# VU_LED.net
KiCad netlist of a schematic drawn in Altium Designer
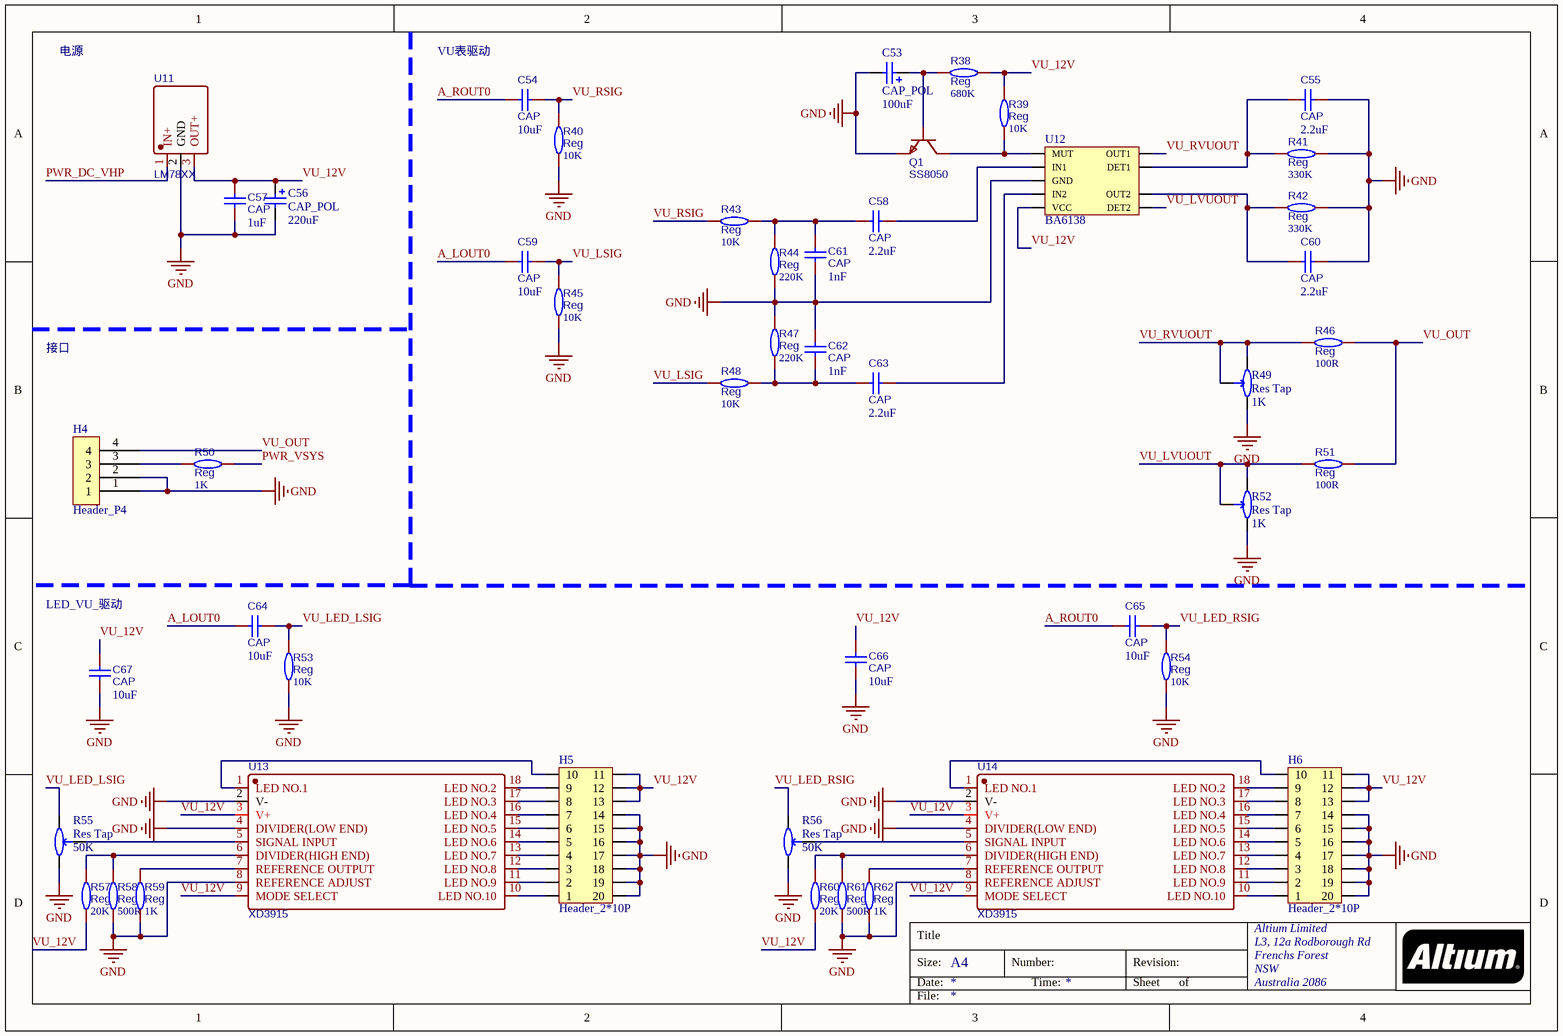
[diagram p0: VU_LED.SchDoc]

(export (version "E")
  (design (tool "Eeschema 10.0.6"))
  (components
    (comp (ref "C53")
      (value "CAP_POL")
      (footprint "CAP_SMD_6.3mm")
      (description "极性电容")
      (fields (field (name "ALTIUM_VALUE") "100uF"))
      (libsource (lib "Levent_lib") (part "CAP_POL"))
    )
    (comp (ref "C54")
      (value "CAP")
      (footprint "C0603")
      (description "Cap")
      (fields
        (field (name "BOM_SUPPLIER PART") "C302008")
        (field (name "BOM_MANUFACTURER PART") "0603B103K101CT")
        (field (name "ALTIUM_VALUE") "10uF")
        (field (name "CONTRIBUTOR") "LCSC")
      )
      (libsource (lib "Levent_lib") (part "CAP"))
    )
    (comp (ref "C55")
      (value "CAP")
      (footprint "C0603")
      (description "Cap")
      (fields
        (field (name "BOM_SUPPLIER PART") "C302008")
        (field (name "BOM_MANUFACTURER PART") "0603B103K101CT")
        (field (name "ALTIUM_VALUE") "2.2uF")
        (field (name "CONTRIBUTOR") "LCSC")
      )
      (libsource (lib "Levent_lib") (part "CAP"))
    )
    (comp (ref "C56")
      (value "CAP_POL")
      (footprint "CAP_SMD_6.3mm")
      (description "极性电容")
      (fields (field (name "ALTIUM_VALUE") "220uF"))
      (libsource (lib "Levent_lib") (part "CAP_POL"))
    )
    (comp (ref "C57")
      (value "CAP")
      (footprint "C0603")
      (description "Cap")
      (fields
        (field (name "BOM_SUPPLIER PART") "C302008")
        (field (name "BOM_MANUFACTURER PART") "0603B103K101CT")
        (field (name "ALTIUM_VALUE") "1uF")
        (field (name "CONTRIBUTOR") "LCSC")
      )
      (libsource (lib "Levent_lib") (part "CAP"))
    )
    (comp (ref "C58")
      (value "CAP")
      (footprint "C0603")
      (description "Cap")
      (fields
        (field (name "BOM_SUPPLIER PART") "C302008")
        (field (name "BOM_MANUFACTURER PART") "0603B103K101CT")
        (field (name "ALTIUM_VALUE") "2.2uF")
        (field (name "CONTRIBUTOR") "LCSC")
      )
      (libsource (lib "Levent_lib") (part "CAP"))
    )
    (comp (ref "C59")
      (value "CAP")
      (footprint "C0603")
      (description "Cap")
      (fields
        (field (name "BOM_SUPPLIER PART") "C302008")
        (field (name "BOM_MANUFACTURER PART") "0603B103K101CT")
        (field (name "ALTIUM_VALUE") "10uF")
        (field (name "CONTRIBUTOR") "LCSC")
      )
      (libsource (lib "Levent_lib") (part "CAP"))
    )
    (comp (ref "C60")
      (value "CAP")
      (footprint "C0603")
      (description "Cap")
      (fields
        (field (name "BOM_SUPPLIER PART") "C302008")
        (field (name "BOM_MANUFACTURER PART") "0603B103K101CT")
        (field (name "ALTIUM_VALUE") "2.2uF")
        (field (name "CONTRIBUTOR") "LCSC")
      )
      (libsource (lib "Levent_lib") (part "CAP"))
    )
    (comp (ref "C61")
      (value "CAP")
      (footprint "C0603")
      (description "Cap")
      (fields
        (field (name "BOM_SUPPLIER PART") "C302008")
        (field (name "BOM_MANUFACTURER PART") "0603B103K101CT")
        (field (name "ALTIUM_VALUE") "1nF")
        (field (name "CONTRIBUTOR") "LCSC")
      )
      (libsource (lib "Levent_lib") (part "CAP"))
    )
    (comp (ref "C62")
      (value "CAP")
      (footprint "C0603")
      (description "Cap")
      (fields
        (field (name "BOM_SUPPLIER PART") "C302008")
        (field (name "BOM_MANUFACTURER PART") "0603B103K101CT")
        (field (name "ALTIUM_VALUE") "1nF")
        (field (name "CONTRIBUTOR") "LCSC")
      )
      (libsource (lib "Levent_lib") (part "CAP"))
    )
    (comp (ref "C63")
      (value "CAP")
      (footprint "C0603")
      (description "Cap")
      (fields
        (field (name "BOM_SUPPLIER PART") "C302008")
        (field (name "BOM_MANUFACTURER PART") "0603B103K101CT")
        (field (name "ALTIUM_VALUE") "2.2uF")
        (field (name "CONTRIBUTOR") "LCSC")
      )
      (libsource (lib "Levent_lib") (part "CAP"))
    )
    (comp (ref "C64")
      (value "CAP")
      (footprint "C0603")
      (description "Cap")
      (fields
        (field (name "BOM_SUPPLIER PART") "C302008")
        (field (name "BOM_MANUFACTURER PART") "0603B103K101CT")
        (field (name "ALTIUM_VALUE") "10uF")
        (field (name "CONTRIBUTOR") "LCSC")
      )
      (libsource (lib "Levent_lib") (part "CAP"))
    )
    (comp (ref "C65")
      (value "CAP")
      (footprint "C0603")
      (description "Cap")
      (fields
        (field (name "BOM_SUPPLIER PART") "C302008")
        (field (name "BOM_MANUFACTURER PART") "0603B103K101CT")
        (field (name "ALTIUM_VALUE") "10uF")
        (field (name "CONTRIBUTOR") "LCSC")
      )
      (libsource (lib "Levent_lib") (part "CAP"))
    )
    (comp (ref "C66")
      (value "CAP")
      (footprint "C0603")
      (description "Cap")
      (fields
        (field (name "BOM_SUPPLIER PART") "C302008")
        (field (name "BOM_MANUFACTURER PART") "0603B103K101CT")
        (field (name "ALTIUM_VALUE") "10uF")
        (field (name "CONTRIBUTOR") "LCSC")
      )
      (libsource (lib "Levent_lib") (part "CAP"))
    )
    (comp (ref "C67")
      (value "CAP")
      (footprint "C0603")
      (description "Cap")
      (fields
        (field (name "BOM_SUPPLIER PART") "C302008")
        (field (name "BOM_MANUFACTURER PART") "0603B103K101CT")
        (field (name "ALTIUM_VALUE") "10uF")
        (field (name "CONTRIBUTOR") "LCSC")
      )
      (libsource (lib "Levent_lib") (part "CAP"))
    )
    (comp (ref "H4")
      (value "Header_P4")
      (footprint "PH_4Pin")
      (description "4Pin排针")
      (libsource (lib "Levent_lib") (part "Header_P4"))
    )
    (comp (ref "H5")
      (value "Header_2*10P")
      (footprint "H_2.0_10x2Pin")
      (description "2*10P连接器")
      (libsource (lib "Levent_lib") (part "Header_2*10P"))
    )
    (comp (ref "H6")
      (value "Header_2*10P")
      (footprint "H_2.0_10x2Pin")
      (description "2*10P连接器")
      (libsource (lib "Levent_lib") (part "Header_2*10P"))
    )
    (comp (ref "Q1")
      (value "SS8050")
      (footprint "SOT-23-3")
      (description "NPN")
      (fields (field (name "BOM_SUPPLIER PART") "C541705") (field (name "CONTRIBUTOR") "LCSC"))
      (libsource (lib "Levent_lib") (part "SS8050"))
    )
    (comp (ref "R38")
      (value "Reg")
      (footprint "R0603")
      (description "电阻")
      (fields
        (field (name "BOM_SUPPLIER PART") "C465721")
        (field (name "BOM_MANUFACTURER PART") "AR03BTCX1002A")
        (field (name "ALTIUM_VALUE") "680K")
        (field (name "CONTRIBUTOR") "LCSC")
      )
      (libsource (lib "Levent_lib") (part "Res"))
    )
    (comp (ref "R39")
      (value "Reg")
      (footprint "R0603")
      (description "电阻")
      (fields
        (field (name "BOM_SUPPLIER PART") "C465721")
        (field (name "BOM_MANUFACTURER PART") "AR03BTCX1002A")
        (field (name "ALTIUM_VALUE") "10K")
        (field (name "CONTRIBUTOR") "LCSC")
      )
      (libsource (lib "Levent_lib") (part "Res"))
    )
    (comp (ref "R40")
      (value "Reg")
      (footprint "R0603")
      (description "电阻")
      (fields
        (field (name "BOM_SUPPLIER PART") "C465721")
        (field (name "BOM_MANUFACTURER PART") "AR03BTCX1002A")
        (field (name "ALTIUM_VALUE") "10K")
        (field (name "CONTRIBUTOR") "LCSC")
      )
      (libsource (lib "Levent_lib") (part "Res"))
    )
    (comp (ref "R41")
      (value "Reg")
      (footprint "R0603")
      (description "电阻")
      (fields
        (field (name "BOM_SUPPLIER PART") "C465721")
        (field (name "BOM_MANUFACTURER PART") "AR03BTCX1002A")
        (field (name "ALTIUM_VALUE") "330K")
        (field (name "CONTRIBUTOR") "LCSC")
      )
      (libsource (lib "Levent_lib") (part "Res"))
    )
    (comp (ref "R42")
      (value "Reg")
      (footprint "R0603")
      (description "电阻")
      (fields
        (field (name "BOM_SUPPLIER PART") "C465721")
        (field (name "BOM_MANUFACTURER PART") "AR03BTCX1002A")
        (field (name "ALTIUM_VALUE") "330K")
        (field (name "CONTRIBUTOR") "LCSC")
      )
      (libsource (lib "Levent_lib") (part "Res"))
    )
    (comp (ref "R43")
      (value "Reg")
      (footprint "R0603")
      (description "电阻")
      (fields
        (field (name "BOM_SUPPLIER PART") "C465721")
        (field (name "BOM_MANUFACTURER PART") "AR03BTCX1002A")
        (field (name "ALTIUM_VALUE") "10K")
        (field (name "CONTRIBUTOR") "LCSC")
      )
      (libsource (lib "Levent_lib") (part "Res"))
    )
    (comp (ref "R44")
      (value "Reg")
      (footprint "R0603")
      (description "电阻")
      (fields
        (field (name "BOM_SUPPLIER PART") "C465721")
        (field (name "BOM_MANUFACTURER PART") "AR03BTCX1002A")
        (field (name "ALTIUM_VALUE") "220K")
        (field (name "CONTRIBUTOR") "LCSC")
      )
      (libsource (lib "Levent_lib") (part "Res"))
    )
    (comp (ref "R45")
      (value "Reg")
      (footprint "R0603")
      (description "电阻")
      (fields
        (field (name "BOM_SUPPLIER PART") "C465721")
        (field (name "BOM_MANUFACTURER PART") "AR03BTCX1002A")
        (field (name "ALTIUM_VALUE") "10K")
        (field (name "CONTRIBUTOR") "LCSC")
      )
      (libsource (lib "Levent_lib") (part "Res"))
    )
    (comp (ref "R46")
      (value "Reg")
      (footprint "R0603")
      (description "电阻")
      (fields
        (field (name "BOM_SUPPLIER PART") "C465721")
        (field (name "BOM_MANUFACTURER PART") "AR03BTCX1002A")
        (field (name "ALTIUM_VALUE") "100R")
        (field (name "CONTRIBUTOR") "LCSC")
      )
      (libsource (lib "Levent_lib") (part "Res"))
    )
    (comp (ref "R47")
      (value "Reg")
      (footprint "R0603")
      (description "电阻")
      (fields
        (field (name "BOM_SUPPLIER PART") "C465721")
        (field (name "BOM_MANUFACTURER PART") "AR03BTCX1002A")
        (field (name "ALTIUM_VALUE") "220K")
        (field (name "CONTRIBUTOR") "LCSC")
      )
      (libsource (lib "Levent_lib") (part "Res"))
    )
    (comp (ref "R48")
      (value "Reg")
      (footprint "R0603")
      (description "电阻")
      (fields
        (field (name "BOM_SUPPLIER PART") "C465721")
        (field (name "BOM_MANUFACTURER PART") "AR03BTCX1002A")
        (field (name "ALTIUM_VALUE") "10K")
        (field (name "CONTRIBUTOR") "LCSC")
      )
      (libsource (lib "Levent_lib") (part "Res"))
    )
    (comp (ref "R49")
      (value "Res Tap")
      (footprint "RES_TAP_HOR")
      (description "可调电阻")
      (fields (field (name "ALTIUM_VALUE") "1K") (field (name "PUBLISHER") "Altium Limited"))
      (libsource (lib "Levent_lib") (part "Res Tap"))
    )
    (comp (ref "R50")
      (value "Reg")
      (footprint "R0603")
      (description "电阻")
      (fields
        (field (name "BOM_SUPPLIER PART") "C465721")
        (field (name "BOM_MANUFACTURER PART") "AR03BTCX1002A")
        (field (name "ALTIUM_VALUE") "1K")
        (field (name "CONTRIBUTOR") "LCSC")
      )
      (libsource (lib "Levent_lib") (part "Res"))
    )
    (comp (ref "R51")
      (value "Reg")
      (footprint "R0603")
      (description "电阻")
      (fields
        (field (name "BOM_SUPPLIER PART") "C465721")
        (field (name "BOM_MANUFACTURER PART") "AR03BTCX1002A")
        (field (name "ALTIUM_VALUE") "100R")
        (field (name "CONTRIBUTOR") "LCSC")
      )
      (libsource (lib "Levent_lib") (part "Res"))
    )
    (comp (ref "R52")
      (value "Res Tap")
      (footprint "RES_TAP_HOR")
      (description "可调电阻")
      (fields (field (name "ALTIUM_VALUE") "1K") (field (name "PUBLISHER") "Altium Limited"))
      (libsource (lib "Levent_lib") (part "Res Tap"))
    )
    (comp (ref "R53")
      (value "Reg")
      (footprint "R0603")
      (description "电阻")
      (fields
        (field (name "BOM_SUPPLIER PART") "C465721")
        (field (name "BOM_MANUFACTURER PART") "AR03BTCX1002A")
        (field (name "ALTIUM_VALUE") "10K")
        (field (name "CONTRIBUTOR") "LCSC")
      )
      (libsource (lib "Levent_lib") (part "Res"))
    )
    (comp (ref "R54")
      (value "Reg")
      (footprint "R0603")
      (description "电阻")
      (fields
        (field (name "BOM_SUPPLIER PART") "C465721")
        (field (name "BOM_MANUFACTURER PART") "AR03BTCX1002A")
        (field (name "ALTIUM_VALUE") "10K")
        (field (name "CONTRIBUTOR") "LCSC")
      )
      (libsource (lib "Levent_lib") (part "Res"))
    )
    (comp (ref "R55")
      (value "Res Tap")
      (footprint "RES_TAP_HOR")
      (description "可调电阻")
      (fields (field (name "ALTIUM_VALUE") "50K") (field (name "PUBLISHER") "Altium Limited"))
      (libsource (lib "Levent_lib") (part "Res Tap"))
    )
    (comp (ref "R56")
      (value "Res Tap")
      (footprint "RES_TAP_HOR")
      (description "可调电阻")
      (fields (field (name "ALTIUM_VALUE") "50K") (field (name "PUBLISHER") "Altium Limited"))
      (libsource (lib "Levent_lib") (part "Res Tap"))
    )
    (comp (ref "R57")
      (value "Reg")
      (footprint "R0603")
      (description "电阻")
      (fields
        (field (name "BOM_SUPPLIER PART") "C465721")
        (field (name "BOM_MANUFACTURER PART") "AR03BTCX1002A")
        (field (name "ALTIUM_VALUE") "20K")
        (field (name "CONTRIBUTOR") "LCSC")
      )
      (libsource (lib "Levent_lib") (part "Res"))
    )
    (comp (ref "R58")
      (value "Reg")
      (footprint "R0603")
      (description "电阻")
      (fields
        (field (name "BOM_SUPPLIER PART") "C465721")
        (field (name "BOM_MANUFACTURER PART") "AR03BTCX1002A")
        (field (name "ALTIUM_VALUE") "500R")
        (field (name "CONTRIBUTOR") "LCSC")
      )
      (libsource (lib "Levent_lib") (part "Res"))
    )
    (comp (ref "R59")
      (value "Reg")
      (footprint "R0603")
      (description "电阻")
      (fields
        (field (name "BOM_SUPPLIER PART") "C465721")
        (field (name "BOM_MANUFACTURER PART") "AR03BTCX1002A")
        (field (name "ALTIUM_VALUE") "1K")
        (field (name "CONTRIBUTOR") "LCSC")
      )
      (libsource (lib "Levent_lib") (part "Res"))
    )
    (comp (ref "R60")
      (value "Reg")
      (footprint "R0603")
      (description "电阻")
      (fields
        (field (name "BOM_SUPPLIER PART") "C465721")
        (field (name "BOM_MANUFACTURER PART") "AR03BTCX1002A")
        (field (name "ALTIUM_VALUE") "20K")
        (field (name "CONTRIBUTOR") "LCSC")
      )
      (libsource (lib "Levent_lib") (part "Res"))
    )
    (comp (ref "R61")
      (value "Reg")
      (footprint "R0603")
      (description "电阻")
      (fields
        (field (name "BOM_SUPPLIER PART") "C465721")
        (field (name "BOM_MANUFACTURER PART") "AR03BTCX1002A")
        (field (name "ALTIUM_VALUE") "500R")
        (field (name "CONTRIBUTOR") "LCSC")
      )
      (libsource (lib "Levent_lib") (part "Res"))
    )
    (comp (ref "R62")
      (value "Reg")
      (footprint "R0603")
      (description "电阻")
      (fields
        (field (name "BOM_SUPPLIER PART") "C465721")
        (field (name "BOM_MANUFACTURER PART") "AR03BTCX1002A")
        (field (name "ALTIUM_VALUE") "1K")
        (field (name "CONTRIBUTOR") "LCSC")
      )
      (libsource (lib "Levent_lib") (part "Res"))
    )
    (comp (ref "U11")
      (value "LM78XX")
      (footprint "TO-220-3_2.54_HOR")
      (description "三端稳压(正电压)")
      (fields
        (field (name "BOM_SUPPLIER PART") "C2902509")
        (field (name "BOM_MANUFACTURER PART") "LM7812T")
        (field (name "CONTRIBUTOR") "LCSC")
      )
      (libsource (lib "Levent_lib") (part "LM78XX"))
    )
    (comp (ref "U12")
      (value "BA6138")
      (footprint "SIP9-2.54")
      (description "对数放大器")
      (libsource (lib "Levent_lib") (part "BA6138"))
    )
    (comp (ref "U13")
      (value "XD3915")
      (footprint "DIP-18")
      (description "电平指示")
      (fields (field (name "BOM_SUPPLIER PART") "C609778") (field (name "CONTRIBUTOR") "LCSC"))
      (libsource (lib "Levent_lib") (part "LM3915"))
    )
    (comp (ref "U14")
      (value "XD3915")
      (footprint "DIP-18")
      (description "电平指示")
      (fields (field (name "BOM_SUPPLIER PART") "C609778") (field (name "CONTRIBUTOR") "LCSC"))
      (libsource (lib "Levent_lib") (part "LM3915"))
    )
  )
  (nets
    (net (code "1") (name "/A_LOUT0") (class "Default")
      (node (ref "C59") (pin "1") (pinfunction "1_1") (pintype "passive"))
      (node (ref "C64") (pin "1") (pinfunction "1_1") (pintype "passive"))
    )
    (net (code "2") (name "/A_ROUT0") (class "Default")
      (node (ref "C54") (pin "1") (pinfunction "1_1") (pintype "passive"))
      (node (ref "C65") (pin "1") (pinfunction "1_1") (pintype "passive"))
    )
    (net (code "3") (name "/PWR_DC_VHP") (class "Default")
      (node (ref "U11") (pin "1") (pinfunction "IN+_1") (pintype "passive"))
    )
    (net (code "4") (name "/PWR_VSYS") (class "Default")
      (node (ref "R50") (pin "1") (pinfunction "1_1") (pintype "passive"))
    )
    (net (code "5") (name "/VU_12V") (class "Default")
      (node (ref "C56") (pin "1") (pinfunction "1_1") (pintype "passive"))
      (node (ref "C57") (pin "1") (pinfunction "1_1") (pintype "passive"))
      (node (ref "C66") (pin "1") (pinfunction "1_1") (pintype "passive"))
      (node (ref "C67") (pin "1") (pinfunction "1_1") (pintype "passive"))
      (node (ref "H5") (pin "11") (pinfunction "11_11") (pintype "passive"))
      (node (ref "H5") (pin "12") (pinfunction "12_12") (pintype "passive"))
      (node (ref "H5") (pin "13") (pinfunction "13_13") (pintype "passive"))
      (node (ref "H6") (pin "11") (pinfunction "11_11") (pintype "passive"))
      (node (ref "H6") (pin "12") (pinfunction "12_12") (pintype "passive"))
      (node (ref "H6") (pin "13") (pinfunction "13_13") (pintype "passive"))
      (node (ref "R38") (pin "1") (pinfunction "1_1") (pintype "passive"))
      (node (ref "R39") (pin "2") (pinfunction "2_2") (pintype "passive"))
      (node (ref "R57") (pin "2") (pinfunction "2_2") (pintype "passive"))
      (node (ref "R60") (pin "2") (pinfunction "2_2") (pintype "passive"))
      (node (ref "U11") (pin "3") (pinfunction "OUT+_3") (pintype "passive"))
      (node (ref "U12") (pin "9") (pinfunction "VCC_9") (pintype "passive"))
      (node (ref "U13") (pin "3") (pinfunction "V+_3") (pintype "passive"))
      (node (ref "U13") (pin "9") (pinfunction "MODE_SELECT_9") (pintype "passive"))
      (node (ref "U14") (pin "3") (pinfunction "V+_3") (pintype "passive"))
      (node (ref "U14") (pin "9") (pinfunction "MODE_SELECT_9") (pintype "passive"))
    )
    (net (code "6") (name "/VU_LED_LSIG") (class "Default")
      (node (ref "C64") (pin "2") (pinfunction "2_2") (pintype "passive"))
      (node (ref "R53") (pin "2") (pinfunction "2_2") (pintype "passive"))
      (node (ref "R55") (pin "1") (pinfunction "A_1") (pintype "passive"))
    )
    (net (code "7") (name "/VU_LED_RSIG") (class "Default")
      (node (ref "C65") (pin "2") (pinfunction "2_2") (pintype "passive"))
      (node (ref "R54") (pin "2") (pinfunction "2_2") (pintype "passive"))
      (node (ref "R56") (pin "1") (pinfunction "A_1") (pintype "passive"))
    )
    (net (code "8") (name "/VU_LSIG") (class "Default")
      (node (ref "C59") (pin "2") (pinfunction "2_2") (pintype "passive"))
      (node (ref "R45") (pin "2") (pinfunction "2_2") (pintype "passive"))
      (node (ref "R48") (pin "2") (pinfunction "2_2") (pintype "passive"))
    )
    (net (code "9") (name "/VU_LVUOUT") (class "Default")
      (node (ref "R51") (pin "2") (pinfunction "2_2") (pintype "passive"))
      (node (ref "R52") (pin "2") (pinfunction "B_2") (pintype "passive"))
      (node (ref "R52") (pin "3") (pinfunction "TAP_3") (pintype "passive"))
      (node (ref "U12") (pin "7") (pinfunction "DET2_7") (pintype "passive"))
    )
    (net (code "10") (name "/VU_OUT") (class "Default")
      (node (ref "H4") (pin "4") (pinfunction "4_4") (pintype "passive"))
      (node (ref "R46") (pin "1") (pinfunction "1_1") (pintype "passive"))
      (node (ref "R51") (pin "1") (pinfunction "1_1") (pintype "passive"))
    )
    (net (code "11") (name "/VU_RSIG") (class "Default")
      (node (ref "C54") (pin "2") (pinfunction "2_2") (pintype "passive"))
      (node (ref "R40") (pin "2") (pinfunction "2_2") (pintype "passive"))
      (node (ref "R43") (pin "2") (pinfunction "2_2") (pintype "passive"))
    )
    (net (code "12") (name "/VU_RVUOUT") (class "Default")
      (node (ref "R46") (pin "2") (pinfunction "2_2") (pintype "passive"))
      (node (ref "R49") (pin "2") (pinfunction "B_2") (pintype "passive"))
      (node (ref "R49") (pin "3") (pinfunction "TAP_3") (pintype "passive"))
      (node (ref "U12") (pin "2") (pinfunction "OUT1_2") (pintype "passive"))
    )
    (net (code "13") (name "GND") (class "Default")
      (node (ref "C53") (pin "2") (pinfunction "2_2") (pintype "passive"))
      (node (ref "C55") (pin "1") (pinfunction "1_1") (pintype "passive"))
      (node (ref "C56") (pin "2") (pinfunction "2_2") (pintype "passive"))
      (node (ref "C57") (pin "2") (pinfunction "2_2") (pintype "passive"))
      (node (ref "C60") (pin "1") (pinfunction "1_1") (pintype "passive"))
      (node (ref "C61") (pin "1") (pinfunction "1_1") (pintype "passive"))
      (node (ref "C62") (pin "2") (pinfunction "2_2") (pintype "passive"))
      (node (ref "C66") (pin "2") (pinfunction "2_2") (pintype "passive"))
      (node (ref "C67") (pin "2") (pinfunction "2_2") (pintype "passive"))
      (node (ref "H4") (pin "1") (pinfunction "1_1") (pintype "passive"))
      (node (ref "H4") (pin "2") (pinfunction "2_2") (pintype "passive"))
      (node (ref "H5") (pin "14") (pinfunction "14_14") (pintype "passive"))
      (node (ref "H5") (pin "15") (pinfunction "15_15") (pintype "passive"))
      (node (ref "H5") (pin "16") (pinfunction "16_16") (pintype "passive"))
      (node (ref "H5") (pin "17") (pinfunction "17_17") (pintype "passive"))
      (node (ref "H5") (pin "18") (pinfunction "18_18") (pintype "passive"))
      (node (ref "H5") (pin "19") (pinfunction "19_19") (pintype "passive"))
      (node (ref "H5") (pin "20") (pinfunction "20_20") (pintype "passive"))
      (node (ref "H6") (pin "14") (pinfunction "14_14") (pintype "passive"))
      (node (ref "H6") (pin "15") (pinfunction "15_15") (pintype "passive"))
      (node (ref "H6") (pin "16") (pinfunction "16_16") (pintype "passive"))
      (node (ref "H6") (pin "17") (pinfunction "17_17") (pintype "passive"))
      (node (ref "H6") (pin "18") (pinfunction "18_18") (pintype "passive"))
      (node (ref "H6") (pin "19") (pinfunction "19_19") (pintype "passive"))
      (node (ref "H6") (pin "20") (pinfunction "20_20") (pintype "passive"))
      (node (ref "Q1") (pin "2") (pinfunction "E_2") (pintype "passive"))
      (node (ref "R40") (pin "1") (pinfunction "1_1") (pintype "passive"))
      (node (ref "R41") (pin "1") (pinfunction "1_1") (pintype "passive"))
      (node (ref "R42") (pin "1") (pinfunction "1_1") (pintype "passive"))
      (node (ref "R44") (pin "2") (pinfunction "2_2") (pintype "passive"))
      (node (ref "R45") (pin "1") (pinfunction "1_1") (pintype "passive"))
      (node (ref "R47") (pin "1") (pinfunction "1_1") (pintype "passive"))
      (node (ref "R49") (pin "1") (pinfunction "A_1") (pintype "passive"))
      (node (ref "R52") (pin "1") (pinfunction "A_1") (pintype "passive"))
      (node (ref "R53") (pin "1") (pinfunction "1_1") (pintype "passive"))
      (node (ref "R54") (pin "1") (pinfunction "1_1") (pintype "passive"))
      (node (ref "R55") (pin "2") (pinfunction "B_2") (pintype "passive"))
      (node (ref "R56") (pin "2") (pinfunction "B_2") (pintype "passive"))
      (node (ref "R58") (pin "2") (pinfunction "2_2") (pintype "passive"))
      (node (ref "R59") (pin "2") (pinfunction "2_2") (pintype "passive"))
      (node (ref "R61") (pin "2") (pinfunction "2_2") (pintype "passive"))
      (node (ref "R62") (pin "2") (pinfunction "2_2") (pintype "passive"))
      (node (ref "U11") (pin "2") (pinfunction "GND_2") (pintype "passive"))
      (node (ref "U12") (pin "5") (pinfunction "GND_5") (pintype "passive"))
      (node (ref "U13") (pin "2") (pinfunction "V-_2") (pintype "passive"))
      (node (ref "U13") (pin "4") (pinfunction "DIVIDER(LOW_END)_4") (pintype "passive"))
      (node (ref "U13") (pin "8") (pinfunction "REFERENCE_ADJUST_8") (pintype "passive"))
      (node (ref "U14") (pin "2") (pinfunction "V-_2") (pintype "passive"))
      (node (ref "U14") (pin "4") (pinfunction "DIVIDER(LOW_END)_4") (pintype "passive"))
      (node (ref "U14") (pin "8") (pinfunction "REFERENCE_ADJUST_8") (pintype "passive"))
    )
    (net (code "14") (name "Net-(C58-Pad1)") (class "Default")
      (node (ref "C58") (pin "1") (pinfunction "1_1") (pintype "passive"))
      (node (ref "C61") (pin "2") (pinfunction "2_2") (pintype "passive"))
      (node (ref "R43") (pin "1") (pinfunction "1_1") (pintype "passive"))
      (node (ref "R44") (pin "1") (pinfunction "1_1") (pintype "passive"))
    )
    (net (code "15") (name "Net-(C62-Pad1)") (class "Default")
      (node (ref "C62") (pin "1") (pinfunction "1_1") (pintype "passive"))
      (node (ref "C63") (pin "1") (pinfunction "1_1") (pintype "passive"))
      (node (ref "R47") (pin "2") (pinfunction "2_2") (pintype "passive"))
      (node (ref "R48") (pin "1") (pinfunction "1_1") (pintype "passive"))
    )
    (net (code "16") (name "Net-(H4-Pad3)") (class "Default")
      (node (ref "H4") (pin "3") (pinfunction "3_3") (pintype "passive"))
      (node (ref "R50") (pin "2") (pinfunction "2_2") (pintype "passive"))
    )
    (net (code "17") (name "Net-(Q1-B)") (class "Default")
      (node (ref "C53") (pin "1") (pinfunction "1_1") (pintype "passive"))
      (node (ref "Q1") (pin "1") (pinfunction "B_1") (pintype "passive"))
      (node (ref "R38") (pin "2") (pinfunction "2_2") (pintype "passive"))
    )
    (net (code "18") (name "Net-(Q1-C)") (class "Default")
      (node (ref "Q1") (pin "3") (pinfunction "C_3") (pintype "passive"))
      (node (ref "R39") (pin "1") (pinfunction "1_1") (pintype "passive"))
      (node (ref "U12") (pin "1") (pinfunction "MUT_1") (pintype "passive"))
    )
    (net (code "19") (name "Net-(R55-TAP)") (class "Default")
      (node (ref "R55") (pin "3") (pinfunction "TAP_3") (pintype "passive"))
      (node (ref "U13") (pin "5") (pinfunction "SIGNAL_INPUT_5") (pintype "passive"))
    )
    (net (code "20") (name "Net-(R56-TAP)") (class "Default")
      (node (ref "R56") (pin "3") (pinfunction "TAP_3") (pintype "passive"))
      (node (ref "U14") (pin "5") (pinfunction "SIGNAL_INPUT_5") (pintype "passive"))
    )
    (net (code "21") (name "Net-(U12-DET1)") (class "Default")
      (node (ref "C55") (pin "2") (pinfunction "2_2") (pintype "passive"))
      (node (ref "R41") (pin "2") (pinfunction "2_2") (pintype "passive"))
      (node (ref "U12") (pin "3") (pinfunction "DET1_3") (pintype "passive"))
    )
    (net (code "22") (name "Net-(U12-IN1)") (class "Default")
      (node (ref "C58") (pin "2") (pinfunction "2_2") (pintype "passive"))
      (node (ref "U12") (pin "4") (pinfunction "IN1_4") (pintype "passive"))
    )
    (net (code "23") (name "Net-(U12-IN2)") (class "Default")
      (node (ref "C63") (pin "2") (pinfunction "2_2") (pintype "passive"))
      (node (ref "U12") (pin "6") (pinfunction "IN2_6") (pintype "passive"))
    )
    (net (code "24") (name "Net-(U12-OUT2)") (class "Default")
      (node (ref "C60") (pin "2") (pinfunction "2_2") (pintype "passive"))
      (node (ref "R42") (pin "2") (pinfunction "2_2") (pintype "passive"))
      (node (ref "U12") (pin "8") (pinfunction "OUT2_8") (pintype "passive"))
    )
    (net (code "25") (name "Net-(U13-DIVIDER(HIGH_END))") (class "Default")
      (node (ref "R57") (pin "1") (pinfunction "1_1") (pintype "passive"))
      (node (ref "R58") (pin "1") (pinfunction "1_1") (pintype "passive"))
      (node (ref "U13") (pin "6") (pinfunction "DIVIDER(HIGH_END)_6") (pintype "passive"))
    )
    (net (code "26") (name "Net-(U13-LED_NO.1)") (class "Default")
      (node (ref "H5") (pin "10") (pinfunction "10_10") (pintype "passive"))
      (node (ref "U13") (pin "1") (pinfunction "LED_NO.1_1") (pintype "passive"))
    )
    (net (code "27") (name "Net-(U13-LED_NO.2)") (class "Default")
      (node (ref "H5") (pin "9") (pinfunction "9_9") (pintype "passive"))
      (node (ref "U13") (pin "18") (pinfunction "LED_NO.2_18") (pintype "passive"))
    )
    (net (code "28") (name "Net-(U13-LED_NO.3)") (class "Default")
      (node (ref "H5") (pin "8") (pinfunction "8_8") (pintype "passive"))
      (node (ref "U13") (pin "17") (pinfunction "LED_NO.3_17") (pintype "passive"))
    )
    (net (code "29") (name "Net-(U13-LED_NO.4)") (class "Default")
      (node (ref "H5") (pin "7") (pinfunction "7_7") (pintype "passive"))
      (node (ref "U13") (pin "16") (pinfunction "LED_NO.4_16") (pintype "passive"))
    )
    (net (code "30") (name "Net-(U13-LED_NO.5)") (class "Default")
      (node (ref "H5") (pin "6") (pinfunction "6_6") (pintype "passive"))
      (node (ref "U13") (pin "15") (pinfunction "LED_NO.5_15") (pintype "passive"))
    )
    (net (code "31") (name "Net-(U13-LED_NO.6)") (class "Default")
      (node (ref "H5") (pin "5") (pinfunction "5_5") (pintype "passive"))
      (node (ref "U13") (pin "14") (pinfunction "LED_NO.6_14") (pintype "passive"))
    )
    (net (code "32") (name "Net-(U13-LED_NO.7)") (class "Default")
      (node (ref "H5") (pin "4") (pinfunction "4_4") (pintype "passive"))
      (node (ref "U13") (pin "13") (pinfunction "LED_NO.7_13") (pintype "passive"))
    )
    (net (code "33") (name "Net-(U13-LED_NO.8)") (class "Default")
      (node (ref "H5") (pin "3") (pinfunction "3_3") (pintype "passive"))
      (node (ref "U13") (pin "12") (pinfunction "LED_NO.8_12") (pintype "passive"))
    )
    (net (code "34") (name "Net-(U13-LED_NO.9)") (class "Default")
      (node (ref "H5") (pin "2") (pinfunction "2_2") (pintype "passive"))
      (node (ref "U13") (pin "11") (pinfunction "LED_NO.9_11") (pintype "passive"))
    )
    (net (code "35") (name "Net-(U13-LED_NO.10)") (class "Default")
      (node (ref "H5") (pin "1") (pinfunction "1_1") (pintype "passive"))
      (node (ref "U13") (pin "10") (pinfunction "LED_NO.10_10") (pintype "passive"))
    )
    (net (code "36") (name "Net-(U13-REFERENCE_OUTPUT)") (class "Default")
      (node (ref "R59") (pin "1") (pinfunction "1_1") (pintype "passive"))
      (node (ref "U13") (pin "7") (pinfunction "REFERENCE_OUTPUT_7") (pintype "passive"))
    )
    (net (code "37") (name "Net-(U14-DIVIDER(HIGH_END))") (class "Default")
      (node (ref "R60") (pin "1") (pinfunction "1_1") (pintype "passive"))
      (node (ref "R61") (pin "1") (pinfunction "1_1") (pintype "passive"))
      (node (ref "U14") (pin "6") (pinfunction "DIVIDER(HIGH_END)_6") (pintype "passive"))
    )
    (net (code "38") (name "Net-(U14-LED_NO.1)") (class "Default")
      (node (ref "H6") (pin "10") (pinfunction "10_10") (pintype "passive"))
      (node (ref "U14") (pin "1") (pinfunction "LED_NO.1_1") (pintype "passive"))
    )
    (net (code "39") (name "Net-(U14-LED_NO.2)") (class "Default")
      (node (ref "H6") (pin "9") (pinfunction "9_9") (pintype "passive"))
      (node (ref "U14") (pin "18") (pinfunction "LED_NO.2_18") (pintype "passive"))
    )
    (net (code "40") (name "Net-(U14-LED_NO.3)") (class "Default")
      (node (ref "H6") (pin "8") (pinfunction "8_8") (pintype "passive"))
      (node (ref "U14") (pin "17") (pinfunction "LED_NO.3_17") (pintype "passive"))
    )
    (net (code "41") (name "Net-(U14-LED_NO.4)") (class "Default")
      (node (ref "H6") (pin "7") (pinfunction "7_7") (pintype "passive"))
      (node (ref "U14") (pin "16") (pinfunction "LED_NO.4_16") (pintype "passive"))
    )
    (net (code "42") (name "Net-(U14-LED_NO.5)") (class "Default")
      (node (ref "H6") (pin "6") (pinfunction "6_6") (pintype "passive"))
      (node (ref "U14") (pin "15") (pinfunction "LED_NO.5_15") (pintype "passive"))
    )
    (net (code "43") (name "Net-(U14-LED_NO.6)") (class "Default")
      (node (ref "H6") (pin "5") (pinfunction "5_5") (pintype "passive"))
      (node (ref "U14") (pin "14") (pinfunction "LED_NO.6_14") (pintype "passive"))
    )
    (net (code "44") (name "Net-(U14-LED_NO.7)") (class "Default")
      (node (ref "H6") (pin "4") (pinfunction "4_4") (pintype "passive"))
      (node (ref "U14") (pin "13") (pinfunction "LED_NO.7_13") (pintype "passive"))
    )
    (net (code "45") (name "Net-(U14-LED_NO.8)") (class "Default")
      (node (ref "H6") (pin "3") (pinfunction "3_3") (pintype "passive"))
      (node (ref "U14") (pin "12") (pinfunction "LED_NO.8_12") (pintype "passive"))
    )
    (net (code "46") (name "Net-(U14-LED_NO.9)") (class "Default")
      (node (ref "H6") (pin "2") (pinfunction "2_2") (pintype "passive"))
      (node (ref "U14") (pin "11") (pinfunction "LED_NO.9_11") (pintype "passive"))
    )
    (net (code "47") (name "Net-(U14-LED_NO.10)") (class "Default")
      (node (ref "H6") (pin "1") (pinfunction "1_1") (pintype "passive"))
      (node (ref "U14") (pin "10") (pinfunction "LED_NO.10_10") (pintype "passive"))
    )
    (net (code "48") (name "Net-(U14-REFERENCE_OUTPUT)") (class "Default")
      (node (ref "R62") (pin "1") (pinfunction "1_1") (pintype "passive"))
      (node (ref "U14") (pin "7") (pinfunction "REFERENCE_OUTPUT_7") (pintype "passive"))
    )
  )
)
